# power.net
KiCad netlist of a schematic drawn in Altium Designer
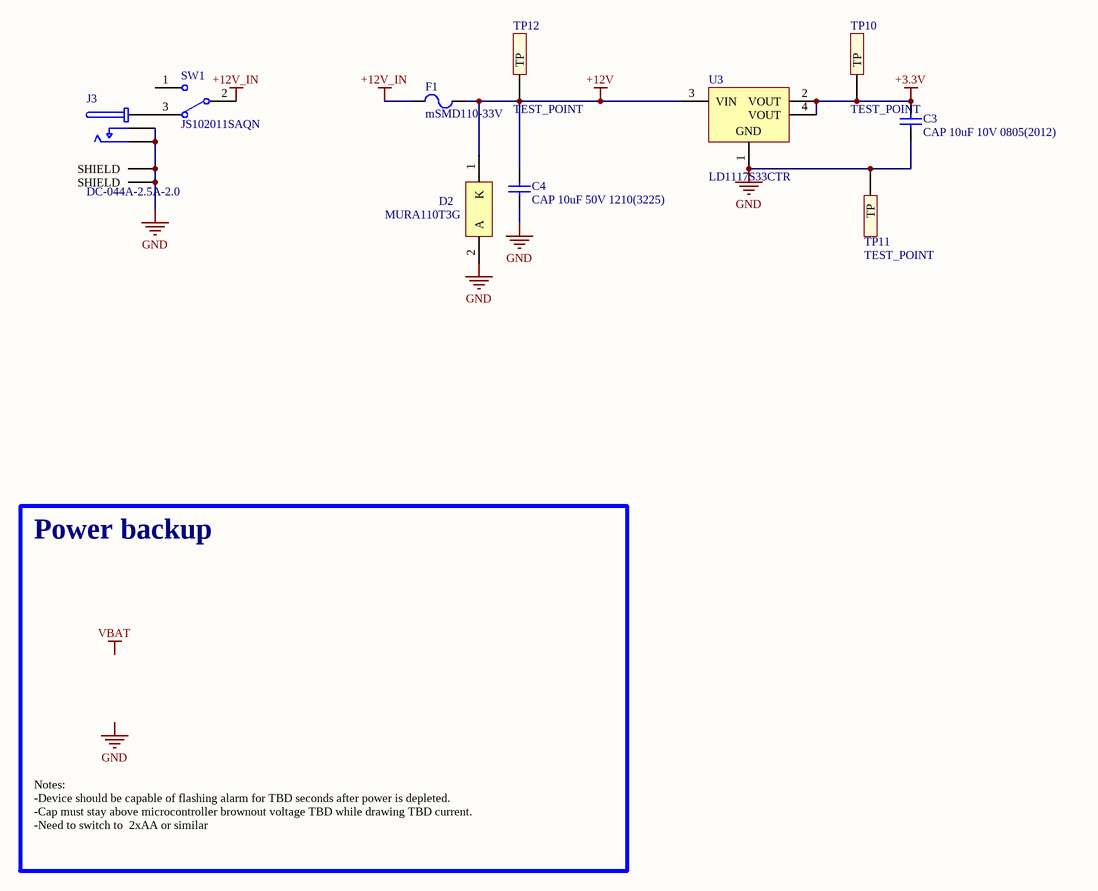
[diagram p0: power.SchDoc]

(export (version "E")
  (design (tool "Eeschema 10.0.6"))
  (components
    (comp (ref "C3")
      (value "CAP 10uF 10V 0805(2012)")
      (footprint "CAPC0805(2012)145_N")
      (description "CAP 10uF 10V ±10% 0805 (2012 Metric) Thickness 1.45mm SMD")
      (fields (field (name "TOLERANCE") "Â±10%"))
      (libsource (lib "Altium Content Vault") (part "CAP"))
    )
    (comp (ref "C4")
      (value "CAP 10uF 50V 1210(3225)")
      (footprint "CAPC1210(3225)190_N")
      (description "CAP 10uF 50V -20% to +80% 1210 (3225 Metric) Thickness 1.9mm SMD")
      (fields (field (name "TOLERANCE") "-20% to +80%"))
      (libsource (lib "Altium Content Vault") (part "CAP"))
    )
    (comp (ref "D2")
      (value "MURA110T3G")
      (footprint "ONSC-SMA-2-403D-02_V")
      (description "Surface Mount Ultrafast Power Rectifier, 2-Pin SMA, Pb-Free, Tape and Reel")
      (fields (field (name "MANUFACTURER") "On Semiconductor"))
      (libsource (lib "Altium Content Vault") (part "ONSC-D-K1A2-2_A"))
    )
    (comp (ref "F1")
      (value "mSMD110-33V")
      (footprint "SEAANDLAND_1812")
      (description "Surface Mount Fuses 33V 100A 1.1A 2.2A 1812 RoHS")
      (fields (field (name "MANUFACTURER") "Sea & Land Electronic Corp"))
      (libsource (lib "Blinkinlabs") (part "mSMD110-33V"))
    )
    (comp (ref "J3")
      (value "DC-044A-2.5A-2.0")
      (footprint "DC-044A-2.5A-2.0")
      (description "DC Jack, 6mm OD, 2mm ID")
      (fields (field (name "MANUFACTURER") "XKB"))
      (libsource (lib "Blinkinlabs") (part "DC-044A-2.5A-2.0"))
    )
    (comp (ref "SW1")
      (value "JS102011SAQN")
      (footprint "CKCP-JS102011SAQN-3_V")
      (description "Sub-Miniature Slide Switch, SPDT, -40 to 85 degC, 3-Pin SMD, RoHS, Tape and Reel")
      (fields (field (name "MANUFACTURER") "C&K Components"))
      (libsource (lib "Altium Content Vault") (part "SW-SPDT-3"))
    )
    (comp (ref "TP10")
      (value "TEST_POINT")
      (footprint "TP-SMD-1mm")
      (description "Test point")
      (libsource (lib "") (part "TEST_POINT_1"))
    )
    (comp (ref "TP11")
      (value "TEST_POINT")
      (footprint "TP-SMD-1mm")
      (description "Test point")
      (libsource (lib "Blinkinlabs") (part "TEST_POINT"))
    )
    (comp (ref "TP12")
      (value "TEST_POINT")
      (footprint "TP-SMD-1mm")
      (description "Test point")
      (libsource (lib "") (part "TEST_POINT_1"))
    )
    (comp (ref "U3")
      (value "LD1117S33CTR")
      (footprint "SOT-223_N")
      (description "Fixed Low Drop Positive Voltage Regulator, 3.3V, 4-Pin SOT-223, Tape and Reel")
      (libsource (lib "Altium Content Vault") (part "PM-REG-LD1117-SOT4"))
    )
  )
  (nets
    (net (code "1") (name "+3.3V") (class "Default")
      (node (ref "C3") (pin "2") (pinfunction "2_2") (pintype "passive"))
      (node (ref "TP10") (pin "1") (pinfunction "TP_1") (pintype "passive"))
      (node (ref "U3") (pin "2") (pinfunction "VOUT_2") (pintype "power_in"))
      (node (ref "U3") (pin "4") (pinfunction "VOUT_4") (pintype "power_in"))
    )
    (net (code "2") (name "+12V") (class "Default")
      (node (ref "C4") (pin "2") (pinfunction "2_2") (pintype "passive"))
      (node (ref "D2") (pin "1") (pinfunction "K_1") (pintype "passive"))
      (node (ref "F1") (pin "2") (pinfunction "2_2") (pintype "passive"))
      (node (ref "TP12") (pin "1") (pinfunction "TP_1") (pintype "passive"))
      (node (ref "U3") (pin "3") (pinfunction "VIN_3") (pintype "power_in"))
    )
    (net (code "3") (name "+12V_IN") (class "Default")
      (node (ref "F1") (pin "1") (pinfunction "1_1") (pintype "passive"))
      (node (ref "SW1") (pin "2") (pinfunction "2_2") (pintype "passive"))
    )
    (net (code "4") (name "GND") (class "Default")
      (node (ref "C3") (pin "1") (pinfunction "1_1") (pintype "passive"))
      (node (ref "C4") (pin "1") (pinfunction "1_1") (pintype "passive"))
      (node (ref "D2") (pin "2") (pinfunction "A_2") (pintype "passive"))
      (node (ref "J3") (pin "2") (pinfunction "2_2") (pintype "passive"))
      (node (ref "J3") (pin "3") (pinfunction "3_3") (pintype "passive"))
      (node (ref "J3") (pin "4") (pinfunction "SHIELD_4") (pintype "passive"))
      (node (ref "J3") (pin "5") (pinfunction "SHIELD_5") (pintype "passive"))
      (node (ref "TP11") (pin "1") (pinfunction "TP_1") (pintype "passive"))
      (node (ref "U3") (pin "1") (pinfunction "GND_1") (pintype "power_in"))
    )
    (net (code "5") (name "Net-(J3-Pad1)") (class "Default")
      (node (ref "J3") (pin "1") (pinfunction "1_1") (pintype "passive"))
      (node (ref "SW1") (pin "3") (pinfunction "3_3") (pintype "passive"))
    )
    (net (code "7") (name "unconnected-(SW1-Pad1)") (class "Default")
      (node (ref "SW1") (pin "1") (pinfunction "1_1") (pintype "passive"))
    )
  )
)
